# Super_Simple_Mosfet_H-Bridge.net
KiCad netlist of a schematic drawn in EAGLE
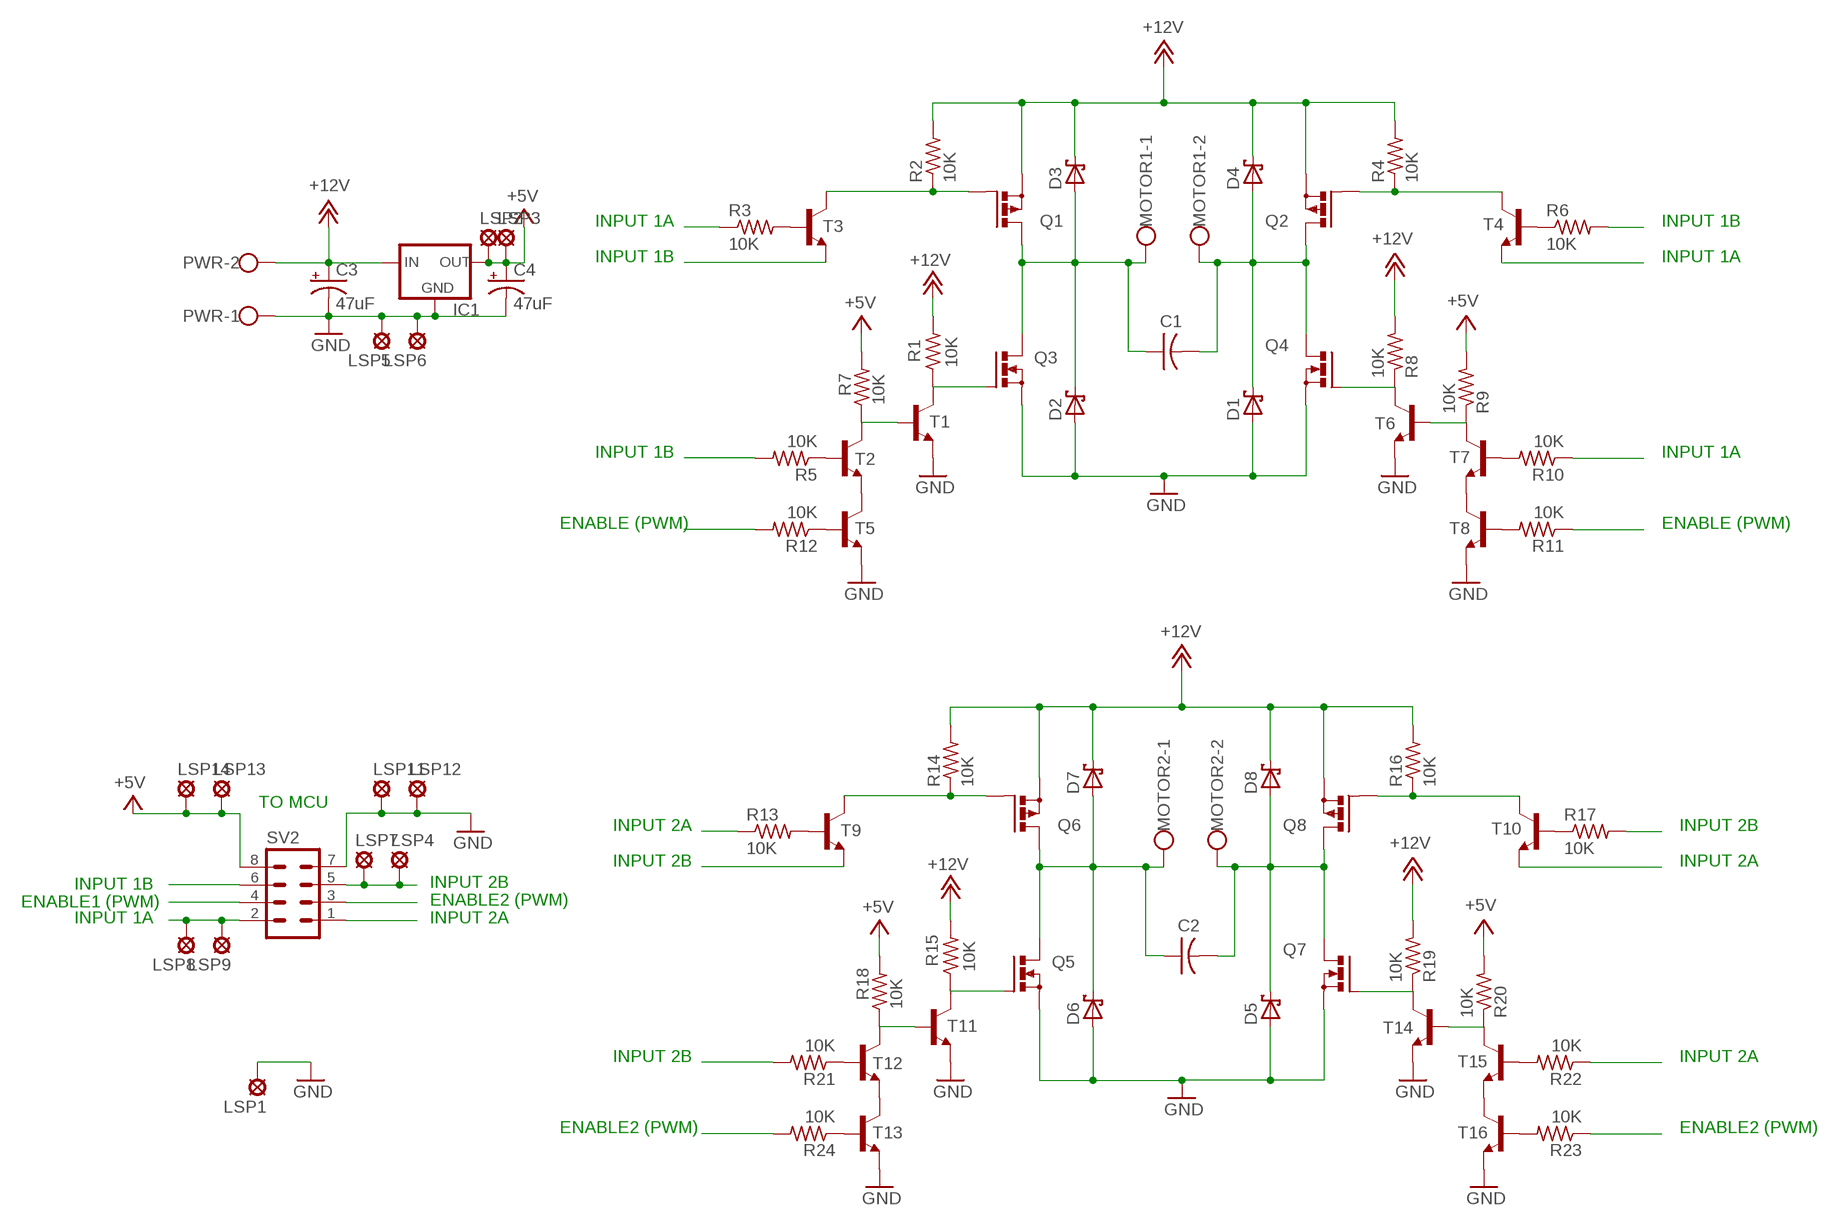
[diagram p0: schematic, sheet 1]

(export (version "E")
  (design (tool "Eeschema 10.0.6"))
  (components
    (comp (ref "C1")
      (value "C-US050-025X075")
      (footprint "eagle-import:C050-025X075")
      (libsource (lib "eagle-import") (part "C-US050-025X075"))
    )
    (comp (ref "C2")
      (value "C-US050-025X075")
      (footprint "eagle-import:C050-025X075")
      (libsource (lib "eagle-import") (part "C-US050-025X075"))
    )
    (comp (ref "C3")
      (value "47uF")
      (footprint "eagle-import:E2,5-6E")
      (libsource (lib "eagle-import") (part "CPOL-USE2,5-6E"))
    )
    (comp (ref "C4")
      (value "47uF")
      (footprint "eagle-import:E2,5-6E")
      (libsource (lib "eagle-import") (part "CPOL-USE2,5-6E"))
    )
    (comp (ref "D1")
      (value "1N5817-B")
      (footprint "eagle-import:DO41-7.6")
      (libsource (lib "eagle-import") (part "1N5817-B"))
    )
    (comp (ref "D2")
      (value "1N5817-B")
      (footprint "eagle-import:DO41-7.6")
      (libsource (lib "eagle-import") (part "1N5817-B"))
    )
    (comp (ref "D3")
      (value "1N5817-B")
      (footprint "eagle-import:DO41-7.6")
      (libsource (lib "eagle-import") (part "1N5817-B"))
    )
    (comp (ref "D4")
      (value "1N5817-B")
      (footprint "eagle-import:DO41-7.6")
      (libsource (lib "eagle-import") (part "1N5817-B"))
    )
    (comp (ref "D5")
      (value "1N5817-B")
      (footprint "eagle-import:DO41-7.6")
      (libsource (lib "eagle-import") (part "1N5817-B"))
    )
    (comp (ref "D6")
      (value "1N5817-B")
      (footprint "eagle-import:DO41-7.6")
      (libsource (lib "eagle-import") (part "1N5817-B"))
    )
    (comp (ref "D7")
      (value "1N5817-B")
      (footprint "eagle-import:DO41-7.6")
      (libsource (lib "eagle-import") (part "1N5817-B"))
    )
    (comp (ref "D8")
      (value "1N5817-B")
      (footprint "eagle-import:DO41-7.6")
      (libsource (lib "eagle-import") (part "1N5817-B"))
    )
    (comp (ref "IC1")
      (value "78XXS")
      (footprint "eagle-import:78XXS")
      (libsource (lib "eagle-import") (part "78XXS"))
    )
    (comp (ref "LSP1")
      (value "LSP13")
      (footprint "eagle-import:LSP13")
      (libsource (lib "eagle-import") (part "LSP13"))
    )
    (comp (ref "LSP2")
      (value "LSP13")
      (footprint "eagle-import:LSP13")
      (libsource (lib "eagle-import") (part "LSP13"))
    )
    (comp (ref "LSP3")
      (value "LSP13")
      (footprint "eagle-import:LSP13")
      (libsource (lib "eagle-import") (part "LSP13"))
    )
    (comp (ref "LSP4")
      (value "LSP13")
      (footprint "eagle-import:LSP13")
      (libsource (lib "eagle-import") (part "LSP13"))
    )
    (comp (ref "LSP5")
      (value "LSP13")
      (footprint "eagle-import:LSP13")
      (libsource (lib "eagle-import") (part "LSP13"))
    )
    (comp (ref "LSP6")
      (value "LSP13")
      (footprint "eagle-import:LSP13")
      (libsource (lib "eagle-import") (part "LSP13"))
    )
    (comp (ref "LSP7")
      (value "LSP13")
      (footprint "eagle-import:LSP13")
      (libsource (lib "eagle-import") (part "LSP13"))
    )
    (comp (ref "LSP8")
      (value "LSP13")
      (footprint "eagle-import:LSP13")
      (libsource (lib "eagle-import") (part "LSP13"))
    )
    (comp (ref "LSP9")
      (value "LSP13")
      (footprint "eagle-import:LSP13")
      (libsource (lib "eagle-import") (part "LSP13"))
    )
    (comp (ref "LSP11")
      (value "LSP13")
      (footprint "eagle-import:LSP13")
      (libsource (lib "eagle-import") (part "LSP13"))
    )
    (comp (ref "LSP12")
      (value "LSP13")
      (footprint "eagle-import:LSP13")
      (libsource (lib "eagle-import") (part "LSP13"))
    )
    (comp (ref "LSP13")
      (value "LSP13")
      (footprint "eagle-import:LSP13")
      (libsource (lib "eagle-import") (part "LSP13"))
    )
    (comp (ref "LSP14")
      (value "LSP13")
      (footprint "eagle-import:LSP13")
      (libsource (lib "eagle-import") (part "LSP13"))
    )
    (comp (ref "MOTOR1")
      (value "W237-102")
      (footprint "eagle-import:W237-102")
      (fields (field (name "MPN") "237-102"))
      (libsource (lib "eagle-import") (part "W237-102"))
    )
    (comp (ref "MOTOR2")
      (value "W237-102")
      (footprint "eagle-import:W237-102")
      (fields (field (name "MPN") "237-102"))
      (libsource (lib "eagle-import") (part "W237-102"))
    )
    (comp (ref "PWR")
      (value "W237-102")
      (footprint "eagle-import:W237-102")
      (fields (field (name "MPN") "237-102"))
      (libsource (lib "eagle-import") (part "W237-102"))
    )
    (comp (ref "Q1")
      (value "IRF9640")
      (footprint "eagle-import:TO220BV")
      (libsource (lib "eagle-import") (part "PMOSFET_PTO220BV"))
    )
    (comp (ref "Q2")
      (value "IRF9640")
      (footprint "eagle-import:TO220BV")
      (libsource (lib "eagle-import") (part "PMOSFET_PTO220BV"))
    )
    (comp (ref "Q3")
      (value "IRF530N")
      (footprint "eagle-import:TO220BV")
      (libsource (lib "eagle-import") (part "PMOSFET_NTO220BV"))
    )
    (comp (ref "Q4")
      (value "IRF530N")
      (footprint "eagle-import:TO220BV")
      (libsource (lib "eagle-import") (part "PMOSFET_NTO220BV"))
    )
    (comp (ref "Q5")
      (value "IRF530N")
      (footprint "eagle-import:TO220BV")
      (libsource (lib "eagle-import") (part "PMOSFET_NTO220BV"))
    )
    (comp (ref "Q6")
      (value "IRF9640")
      (footprint "eagle-import:TO220BV")
      (libsource (lib "eagle-import") (part "PMOSFET_PTO220BV"))
    )
    (comp (ref "Q7")
      (value "IRF530N")
      (footprint "eagle-import:TO220BV")
      (libsource (lib "eagle-import") (part "PMOSFET_NTO220BV"))
    )
    (comp (ref "Q8")
      (value "IRF9640")
      (footprint "eagle-import:TO220BV")
      (libsource (lib "eagle-import") (part "PMOSFET_PTO220BV"))
    )
    (comp (ref "R1")
      (value "10K")
      (footprint "eagle-import:0207_10")
      (libsource (lib "eagle-import") (part "R-US_0207/10"))
    )
    (comp (ref "R2")
      (value "10K")
      (footprint "eagle-import:0207_10")
      (libsource (lib "eagle-import") (part "R-US_0207/10"))
    )
    (comp (ref "R3")
      (value "10K")
      (footprint "eagle-import:0207_10")
      (libsource (lib "eagle-import") (part "R-US_0207/10"))
    )
    (comp (ref "R4")
      (value "10K")
      (footprint "eagle-import:0207_10")
      (libsource (lib "eagle-import") (part "R-US_0207/10"))
    )
    (comp (ref "R5")
      (value "10K")
      (footprint "eagle-import:0207_10")
      (libsource (lib "eagle-import") (part "R-US_0207/10"))
    )
    (comp (ref "R6")
      (value "10K")
      (footprint "eagle-import:0207_10")
      (libsource (lib "eagle-import") (part "R-US_0207/10"))
    )
    (comp (ref "R7")
      (value "10K")
      (footprint "eagle-import:0207_10")
      (libsource (lib "eagle-import") (part "R-US_0207/10"))
    )
    (comp (ref "R8")
      (value "10K")
      (footprint "eagle-import:0207_10")
      (libsource (lib "eagle-import") (part "R-US_0207/10"))
    )
    (comp (ref "R9")
      (value "10K")
      (footprint "eagle-import:0207_10")
      (libsource (lib "eagle-import") (part "R-US_0207/10"))
    )
    (comp (ref "R10")
      (value "10K")
      (footprint "eagle-import:0207_10")
      (libsource (lib "eagle-import") (part "R-US_0207/10"))
    )
    (comp (ref "R11")
      (value "10K")
      (footprint "eagle-import:0207_10")
      (libsource (lib "eagle-import") (part "R-US_0207/10"))
    )
    (comp (ref "R12")
      (value "10K")
      (footprint "eagle-import:0207_10")
      (libsource (lib "eagle-import") (part "R-US_0207/10"))
    )
    (comp (ref "R13")
      (value "10K")
      (footprint "eagle-import:0207_10")
      (libsource (lib "eagle-import") (part "R-US_0207/10"))
    )
    (comp (ref "R14")
      (value "10K")
      (footprint "eagle-import:0207_10")
      (libsource (lib "eagle-import") (part "R-US_0207/10"))
    )
    (comp (ref "R15")
      (value "10K")
      (footprint "eagle-import:0207_10")
      (libsource (lib "eagle-import") (part "R-US_0207/10"))
    )
    (comp (ref "R16")
      (value "10K")
      (footprint "eagle-import:0207_10")
      (libsource (lib "eagle-import") (part "R-US_0207/10"))
    )
    (comp (ref "R17")
      (value "10K")
      (footprint "eagle-import:0207_10")
      (libsource (lib "eagle-import") (part "R-US_0207/10"))
    )
    (comp (ref "R18")
      (value "10K")
      (footprint "eagle-import:0207_10")
      (libsource (lib "eagle-import") (part "R-US_0207/10"))
    )
    (comp (ref "R19")
      (value "10K")
      (footprint "eagle-import:0207_10")
      (libsource (lib "eagle-import") (part "R-US_0207/10"))
    )
    (comp (ref "R20")
      (value "10K")
      (footprint "eagle-import:0207_10")
      (libsource (lib "eagle-import") (part "R-US_0207/10"))
    )
    (comp (ref "R21")
      (value "10K")
      (footprint "eagle-import:0207_10")
      (libsource (lib "eagle-import") (part "R-US_0207/10"))
    )
    (comp (ref "R22")
      (value "10K")
      (footprint "eagle-import:0207_10")
      (libsource (lib "eagle-import") (part "R-US_0207/10"))
    )
    (comp (ref "R23")
      (value "10K")
      (footprint "eagle-import:0207_10")
      (libsource (lib "eagle-import") (part "R-US_0207/10"))
    )
    (comp (ref "R24")
      (value "10K")
      (footprint "eagle-import:0207_10")
      (libsource (lib "eagle-import") (part "R-US_0207/10"))
    )
    (comp (ref "SV2")
      (value "MA04-2")
      (footprint "eagle-import:MA04-2")
      (libsource (lib "eagle-import") (part "MA04-2"))
    )
    (comp (ref "T1")
      (value "-NPN-TO92-EBC")
      (footprint "eagle-import:TO92-EBC")
      (libsource (lib "eagle-import") (part "-NPN-TO92-EBC"))
    )
    (comp (ref "T2")
      (value "-NPN-TO92-EBC")
      (footprint "eagle-import:TO92-EBC")
      (libsource (lib "eagle-import") (part "-NPN-TO92-EBC"))
    )
    (comp (ref "T3")
      (value "-NPN-TO92-EBC")
      (footprint "eagle-import:TO92-EBC")
      (libsource (lib "eagle-import") (part "-NPN-TO92-EBC"))
    )
    (comp (ref "T4")
      (value "-NPN-TO92-EBC")
      (footprint "eagle-import:TO92-EBC")
      (libsource (lib "eagle-import") (part "-NPN-TO92-EBC"))
    )
    (comp (ref "T5")
      (value "-NPN-TO92-EBC")
      (footprint "eagle-import:TO92-EBC")
      (libsource (lib "eagle-import") (part "-NPN-TO92-EBC"))
    )
    (comp (ref "T6")
      (value "-NPN-TO92-EBC")
      (footprint "eagle-import:TO92-EBC")
      (libsource (lib "eagle-import") (part "-NPN-TO92-EBC"))
    )
    (comp (ref "T7")
      (value "-NPN-TO92-EBC")
      (footprint "eagle-import:TO92-EBC")
      (libsource (lib "eagle-import") (part "-NPN-TO92-EBC"))
    )
    (comp (ref "T8")
      (value "-NPN-TO92-EBC")
      (footprint "eagle-import:TO92-EBC")
      (libsource (lib "eagle-import") (part "-NPN-TO92-EBC"))
    )
    (comp (ref "T9")
      (value "-NPN-TO92-EBC")
      (footprint "eagle-import:TO92-EBC")
      (libsource (lib "eagle-import") (part "-NPN-TO92-EBC"))
    )
    (comp (ref "T10")
      (value "-NPN-TO92-EBC")
      (footprint "eagle-import:TO92-EBC")
      (libsource (lib "eagle-import") (part "-NPN-TO92-EBC"))
    )
    (comp (ref "T11")
      (value "-NPN-TO92-EBC")
      (footprint "eagle-import:TO92-EBC")
      (libsource (lib "eagle-import") (part "-NPN-TO92-EBC"))
    )
    (comp (ref "T12")
      (value "-NPN-TO92-EBC")
      (footprint "eagle-import:TO92-EBC")
      (libsource (lib "eagle-import") (part "-NPN-TO92-EBC"))
    )
    (comp (ref "T13")
      (value "-NPN-TO92-EBC")
      (footprint "eagle-import:TO92-EBC")
      (libsource (lib "eagle-import") (part "-NPN-TO92-EBC"))
    )
    (comp (ref "T14")
      (value "-NPN-TO92-EBC")
      (footprint "eagle-import:TO92-EBC")
      (libsource (lib "eagle-import") (part "-NPN-TO92-EBC"))
    )
    (comp (ref "T15")
      (value "-NPN-TO92-EBC")
      (footprint "eagle-import:TO92-EBC")
      (libsource (lib "eagle-import") (part "-NPN-TO92-EBC"))
    )
    (comp (ref "T16")
      (value "-NPN-TO92-EBC")
      (footprint "eagle-import:TO92-EBC")
      (libsource (lib "eagle-import") (part "-NPN-TO92-EBC"))
    )
  )
  (nets
    (net (code "1") (name "+5V") (class "Default")
      (node (ref "C4") (pin "+") (pinfunction "+_+") (pintype "passive"))
      (node (ref "IC1") (pin "OUT") (pinfunction "OUT_OUT") (pintype "passive"))
      (node (ref "LSP13") (pin "MP") (pinfunction "MP_MP") (pintype "passive"))
      (node (ref "LSP14") (pin "MP") (pinfunction "MP_MP") (pintype "passive"))
      (node (ref "LSP2") (pin "MP") (pinfunction "MP_MP") (pintype "passive"))
      (node (ref "LSP3") (pin "MP") (pinfunction "MP_MP") (pintype "passive"))
      (node (ref "R18") (pin "2") (pinfunction "2_2") (pintype "passive"))
      (node (ref "R20") (pin "2") (pinfunction "2_2") (pintype "passive"))
      (node (ref "R7") (pin "2") (pinfunction "2_2") (pintype "passive"))
      (node (ref "R9") (pin "2") (pinfunction "2_2") (pintype "passive"))
      (node (ref "SV2") (pin "8") (pinfunction "8_8") (pintype "passive"))
    )
    (net (code "2") (name "+12V") (class "Default")
      (node (ref "C3") (pin "+") (pinfunction "+_+") (pintype "passive"))
      (node (ref "D3") (pin "C") (pinfunction "C_C") (pintype "passive"))
      (node (ref "D4") (pin "C") (pinfunction "C_C") (pintype "passive"))
      (node (ref "D7") (pin "C") (pinfunction "C_C") (pintype "passive"))
      (node (ref "D8") (pin "C") (pinfunction "C_C") (pintype "passive"))
      (node (ref "IC1") (pin "IN") (pinfunction "IN_IN") (pintype "input"))
      (node (ref "PWR") (pin "2") (pinfunction "KL_2") (pintype "passive"))
      (node (ref "Q1") (pin "S") (pinfunction "S_S") (pintype "passive"))
      (node (ref "Q2") (pin "S") (pinfunction "S_S") (pintype "passive"))
      (node (ref "Q6") (pin "S") (pinfunction "S_S") (pintype "passive"))
      (node (ref "Q8") (pin "S") (pinfunction "S_S") (pintype "passive"))
      (node (ref "R1") (pin "2") (pinfunction "2_2") (pintype "passive"))
      (node (ref "R14") (pin "2") (pinfunction "2_2") (pintype "passive"))
      (node (ref "R15") (pin "2") (pinfunction "2_2") (pintype "passive"))
      (node (ref "R16") (pin "2") (pinfunction "2_2") (pintype "passive"))
      (node (ref "R19") (pin "2") (pinfunction "2_2") (pintype "passive"))
      (node (ref "R2") (pin "2") (pinfunction "2_2") (pintype "passive"))
      (node (ref "R4") (pin "2") (pinfunction "2_2") (pintype "passive"))
      (node (ref "R8") (pin "2") (pinfunction "2_2") (pintype "passive"))
    )
    (net (code "3") (name "/1A") (class "Default")
      (node (ref "LSP8") (pin "MP") (pinfunction "MP_MP") (pintype "passive"))
      (node (ref "LSP9") (pin "MP") (pinfunction "MP_MP") (pintype "passive"))
      (node (ref "R10") (pin "1") (pinfunction "1_1") (pintype "passive"))
      (node (ref "R3") (pin "1") (pinfunction "1_1") (pintype "passive"))
      (node (ref "SV2") (pin "2") (pinfunction "2_2") (pintype "passive"))
      (node (ref "T4") (pin "E") (pinfunction "E_E") (pintype "passive"))
    )
    (net (code "4") (name "/1B") (class "Default")
      (node (ref "R5") (pin "2") (pinfunction "2_2") (pintype "passive"))
      (node (ref "R6") (pin "2") (pinfunction "2_2") (pintype "passive"))
      (node (ref "SV2") (pin "6") (pinfunction "6_6") (pintype "passive"))
      (node (ref "T3") (pin "E") (pinfunction "E_E") (pintype "passive"))
    )
    (net (code "5") (name "/2A") (class "Default")
      (node (ref "R13") (pin "1") (pinfunction "1_1") (pintype "passive"))
      (node (ref "R22") (pin "1") (pinfunction "1_1") (pintype "passive"))
      (node (ref "SV2") (pin "1") (pinfunction "1_1") (pintype "passive"))
      (node (ref "T10") (pin "E") (pinfunction "E_E") (pintype "passive"))
    )
    (net (code "6") (name "/2B") (class "Default")
      (node (ref "LSP4") (pin "MP") (pinfunction "MP_MP") (pintype "passive"))
      (node (ref "LSP7") (pin "MP") (pinfunction "MP_MP") (pintype "passive"))
      (node (ref "R17") (pin "2") (pinfunction "2_2") (pintype "passive"))
      (node (ref "R21") (pin "2") (pinfunction "2_2") (pintype "passive"))
      (node (ref "SV2") (pin "5") (pinfunction "5_5") (pintype "passive"))
      (node (ref "T9") (pin "E") (pinfunction "E_E") (pintype "passive"))
    )
    (net (code "7") (name "/ENABLE1") (class "Default")
      (node (ref "R11") (pin "1") (pinfunction "1_1") (pintype "passive"))
      (node (ref "R12") (pin "2") (pinfunction "2_2") (pintype "passive"))
      (node (ref "SV2") (pin "4") (pinfunction "4_4") (pintype "passive"))
    )
    (net (code "8") (name "/ENABLE2") (class "Default")
      (node (ref "R23") (pin "1") (pinfunction "1_1") (pintype "passive"))
      (node (ref "R24") (pin "2") (pinfunction "2_2") (pintype "passive"))
      (node (ref "SV2") (pin "3") (pinfunction "3_3") (pintype "passive"))
    )
    (net (code "9") (name "GND") (class "Default")
      (node (ref "C3") (pin "-") (pinfunction "-_-") (pintype "passive"))
      (node (ref "C4") (pin "-") (pinfunction "-_-") (pintype "passive"))
      (node (ref "D1") (pin "A") (pinfunction "A_A") (pintype "passive"))
      (node (ref "D2") (pin "A") (pinfunction "A_A") (pintype "passive"))
      (node (ref "D5") (pin "A") (pinfunction "A_A") (pintype "passive"))
      (node (ref "D6") (pin "A") (pinfunction "A_A") (pintype "passive"))
      (node (ref "IC1") (pin "GND") (pinfunction "GND_GND") (pintype "input"))
      (node (ref "LSP1") (pin "MP") (pinfunction "MP_MP") (pintype "passive"))
      (node (ref "LSP11") (pin "MP") (pinfunction "MP_MP") (pintype "passive"))
      (node (ref "LSP12") (pin "MP") (pinfunction "MP_MP") (pintype "passive"))
      (node (ref "LSP5") (pin "MP") (pinfunction "MP_MP") (pintype "passive"))
      (node (ref "LSP6") (pin "MP") (pinfunction "MP_MP") (pintype "passive"))
      (node (ref "PWR") (pin "1") (pinfunction "KL_1") (pintype "passive"))
      (node (ref "Q3") (pin "S") (pinfunction "S_S") (pintype "passive"))
      (node (ref "Q4") (pin "S") (pinfunction "S_S") (pintype "passive"))
      (node (ref "Q5") (pin "S") (pinfunction "S_S") (pintype "passive"))
      (node (ref "Q7") (pin "S") (pinfunction "S_S") (pintype "passive"))
      (node (ref "SV2") (pin "7") (pinfunction "7_7") (pintype "passive"))
      (node (ref "T1") (pin "E") (pinfunction "E_E") (pintype "passive"))
      (node (ref "T11") (pin "E") (pinfunction "E_E") (pintype "passive"))
      (node (ref "T13") (pin "E") (pinfunction "E_E") (pintype "passive"))
      (node (ref "T14") (pin "E") (pinfunction "E_E") (pintype "passive"))
      (node (ref "T16") (pin "E") (pinfunction "E_E") (pintype "passive"))
      (node (ref "T5") (pin "E") (pinfunction "E_E") (pintype "passive"))
      (node (ref "T6") (pin "E") (pinfunction "E_E") (pintype "passive"))
      (node (ref "T8") (pin "E") (pinfunction "E_E") (pintype "passive"))
    )
    (net (code "10") (name "Net-(MOTOR1A-KL)") (class "Default")
      (node (ref "C1") (pin "1") (pinfunction "1_1") (pintype "passive"))
      (node (ref "D2") (pin "C") (pinfunction "C_C") (pintype "passive"))
      (node (ref "D3") (pin "A") (pinfunction "A_A") (pintype "passive"))
      (node (ref "MOTOR1") (pin "1") (pinfunction "KL_1") (pintype "passive"))
      (node (ref "Q1") (pin "D") (pinfunction "D_D") (pintype "passive"))
      (node (ref "Q3") (pin "D") (pinfunction "D_D") (pintype "passive"))
    )
    (net (code "11") (name "Net-(MOTOR1B-KL)") (class "Default")
      (node (ref "C1") (pin "2") (pinfunction "2_2") (pintype "passive"))
      (node (ref "D1") (pin "C") (pinfunction "C_C") (pintype "passive"))
      (node (ref "D4") (pin "A") (pinfunction "A_A") (pintype "passive"))
      (node (ref "MOTOR1") (pin "2") (pinfunction "KL_2") (pintype "passive"))
      (node (ref "Q2") (pin "D") (pinfunction "D_D") (pintype "passive"))
      (node (ref "Q4") (pin "D") (pinfunction "D_D") (pintype "passive"))
    )
    (net (code "12") (name "Net-(MOTOR2A-KL)") (class "Default")
      (node (ref "C2") (pin "1") (pinfunction "1_1") (pintype "passive"))
      (node (ref "D6") (pin "C") (pinfunction "C_C") (pintype "passive"))
      (node (ref "D7") (pin "A") (pinfunction "A_A") (pintype "passive"))
      (node (ref "MOTOR2") (pin "1") (pinfunction "KL_1") (pintype "passive"))
      (node (ref "Q5") (pin "D") (pinfunction "D_D") (pintype "passive"))
      (node (ref "Q6") (pin "D") (pinfunction "D_D") (pintype "passive"))
    )
    (net (code "13") (name "Net-(MOTOR2B-KL)") (class "Default")
      (node (ref "C2") (pin "2") (pinfunction "2_2") (pintype "passive"))
      (node (ref "D5") (pin "C") (pinfunction "C_C") (pintype "passive"))
      (node (ref "D8") (pin "A") (pinfunction "A_A") (pintype "passive"))
      (node (ref "MOTOR2") (pin "2") (pinfunction "KL_2") (pintype "passive"))
      (node (ref "Q7") (pin "D") (pinfunction "D_D") (pintype "passive"))
      (node (ref "Q8") (pin "D") (pinfunction "D_D") (pintype "passive"))
    )
    (net (code "14") (name "Net-(Q1-PadG)") (class "Default")
      (node (ref "Q1") (pin "G") (pinfunction "G_G") (pintype "passive"))
      (node (ref "R2") (pin "1") (pinfunction "1_1") (pintype "passive"))
      (node (ref "T3") (pin "C") (pinfunction "C_C") (pintype "passive"))
    )
    (net (code "15") (name "Net-(Q2-PadG)") (class "Default")
      (node (ref "Q2") (pin "G") (pinfunction "G_G") (pintype "passive"))
      (node (ref "R4") (pin "1") (pinfunction "1_1") (pintype "passive"))
      (node (ref "T4") (pin "C") (pinfunction "C_C") (pintype "passive"))
    )
    (net (code "16") (name "Net-(Q3-PadG)") (class "Default")
      (node (ref "Q3") (pin "G") (pinfunction "G_G") (pintype "passive"))
      (node (ref "R1") (pin "1") (pinfunction "1_1") (pintype "passive"))
      (node (ref "T1") (pin "C") (pinfunction "C_C") (pintype "passive"))
    )
    (net (code "17") (name "Net-(Q4-PadG)") (class "Default")
      (node (ref "Q4") (pin "G") (pinfunction "G_G") (pintype "passive"))
      (node (ref "R8") (pin "1") (pinfunction "1_1") (pintype "passive"))
      (node (ref "T6") (pin "C") (pinfunction "C_C") (pintype "passive"))
    )
    (net (code "18") (name "Net-(Q5-PadG)") (class "Default")
      (node (ref "Q5") (pin "G") (pinfunction "G_G") (pintype "passive"))
      (node (ref "R15") (pin "1") (pinfunction "1_1") (pintype "passive"))
      (node (ref "T11") (pin "C") (pinfunction "C_C") (pintype "passive"))
    )
    (net (code "19") (name "Net-(Q6-PadG)") (class "Default")
      (node (ref "Q6") (pin "G") (pinfunction "G_G") (pintype "passive"))
      (node (ref "R14") (pin "1") (pinfunction "1_1") (pintype "passive"))
      (node (ref "T9") (pin "C") (pinfunction "C_C") (pintype "passive"))
    )
    (net (code "20") (name "Net-(Q7-PadG)") (class "Default")
      (node (ref "Q7") (pin "G") (pinfunction "G_G") (pintype "passive"))
      (node (ref "R19") (pin "1") (pinfunction "1_1") (pintype "passive"))
      (node (ref "T14") (pin "C") (pinfunction "C_C") (pintype "passive"))
    )
    (net (code "21") (name "Net-(Q8-PadG)") (class "Default")
      (node (ref "Q8") (pin "G") (pinfunction "G_G") (pintype "passive"))
      (node (ref "R16") (pin "1") (pinfunction "1_1") (pintype "passive"))
      (node (ref "T10") (pin "C") (pinfunction "C_C") (pintype "passive"))
    )
    (net (code "22") (name "Net-(R3-Pad2)") (class "Default")
      (node (ref "R3") (pin "2") (pinfunction "2_2") (pintype "passive"))
      (node (ref "T3") (pin "B") (pinfunction "B_B") (pintype "passive"))
    )
    (net (code "23") (name "Net-(R5-Pad1)") (class "Default")
      (node (ref "R5") (pin "1") (pinfunction "1_1") (pintype "passive"))
      (node (ref "T2") (pin "B") (pinfunction "B_B") (pintype "passive"))
    )
    (net (code "24") (name "Net-(R6-Pad1)") (class "Default")
      (node (ref "R6") (pin "1") (pinfunction "1_1") (pintype "passive"))
      (node (ref "T4") (pin "B") (pinfunction "B_B") (pintype "passive"))
    )
    (net (code "25") (name "Net-(R7-Pad1)") (class "Default")
      (node (ref "R7") (pin "1") (pinfunction "1_1") (pintype "passive"))
      (node (ref "T1") (pin "B") (pinfunction "B_B") (pintype "passive"))
      (node (ref "T2") (pin "C") (pinfunction "C_C") (pintype "passive"))
    )
    (net (code "26") (name "Net-(R9-Pad1)") (class "Default")
      (node (ref "R9") (pin "1") (pinfunction "1_1") (pintype "passive"))
      (node (ref "T6") (pin "B") (pinfunction "B_B") (pintype "passive"))
      (node (ref "T7") (pin "C") (pinfunction "C_C") (pintype "passive"))
    )
    (net (code "27") (name "Net-(R10-Pad2)") (class "Default")
      (node (ref "R10") (pin "2") (pinfunction "2_2") (pintype "passive"))
      (node (ref "T7") (pin "B") (pinfunction "B_B") (pintype "passive"))
    )
    (net (code "28") (name "Net-(R11-Pad2)") (class "Default")
      (node (ref "R11") (pin "2") (pinfunction "2_2") (pintype "passive"))
      (node (ref "T8") (pin "B") (pinfunction "B_B") (pintype "passive"))
    )
    (net (code "29") (name "Net-(R12-Pad1)") (class "Default")
      (node (ref "R12") (pin "1") (pinfunction "1_1") (pintype "passive"))
      (node (ref "T5") (pin "B") (pinfunction "B_B") (pintype "passive"))
    )
    (net (code "30") (name "Net-(R13-Pad2)") (class "Default")
      (node (ref "R13") (pin "2") (pinfunction "2_2") (pintype "passive"))
      (node (ref "T9") (pin "B") (pinfunction "B_B") (pintype "passive"))
    )
    (net (code "31") (name "Net-(R17-Pad1)") (class "Default")
      (node (ref "R17") (pin "1") (pinfunction "1_1") (pintype "passive"))
      (node (ref "T10") (pin "B") (pinfunction "B_B") (pintype "passive"))
    )
    (net (code "32") (name "Net-(R18-Pad1)") (class "Default")
      (node (ref "R18") (pin "1") (pinfunction "1_1") (pintype "passive"))
      (node (ref "T11") (pin "B") (pinfunction "B_B") (pintype "passive"))
      (node (ref "T12") (pin "C") (pinfunction "C_C") (pintype "passive"))
    )
    (net (code "33") (name "Net-(R20-Pad1)") (class "Default")
      (node (ref "R20") (pin "1") (pinfunction "1_1") (pintype "passive"))
      (node (ref "T14") (pin "B") (pinfunction "B_B") (pintype "passive"))
      (node (ref "T15") (pin "C") (pinfunction "C_C") (pintype "passive"))
    )
    (net (code "34") (name "Net-(R21-Pad1)") (class "Default")
      (node (ref "R21") (pin "1") (pinfunction "1_1") (pintype "passive"))
      (node (ref "T12") (pin "B") (pinfunction "B_B") (pintype "passive"))
    )
    (net (code "35") (name "Net-(R22-Pad2)") (class "Default")
      (node (ref "R22") (pin "2") (pinfunction "2_2") (pintype "passive"))
      (node (ref "T15") (pin "B") (pinfunction "B_B") (pintype "passive"))
    )
    (net (code "36") (name "Net-(R23-Pad2)") (class "Default")
      (node (ref "R23") (pin "2") (pinfunction "2_2") (pintype "passive"))
      (node (ref "T16") (pin "B") (pinfunction "B_B") (pintype "passive"))
    )
    (net (code "37") (name "Net-(R24-Pad1)") (class "Default")
      (node (ref "R24") (pin "1") (pinfunction "1_1") (pintype "passive"))
      (node (ref "T13") (pin "B") (pinfunction "B_B") (pintype "passive"))
    )
    (net (code "38") (name "Net-(T2-PadE)") (class "Default")
      (node (ref "T2") (pin "E") (pinfunction "E_E") (pintype "passive"))
      (node (ref "T5") (pin "C") (pinfunction "C_C") (pintype "passive"))
    )
    (net (code "39") (name "Net-(T7-PadE)") (class "Default")
      (node (ref "T7") (pin "E") (pinfunction "E_E") (pintype "passive"))
      (node (ref "T8") (pin "C") (pinfunction "C_C") (pintype "passive"))
    )
    (net (code "40") (name "Net-(T12-PadE)") (class "Default")
      (node (ref "T12") (pin "E") (pinfunction "E_E") (pintype "passive"))
      (node (ref "T13") (pin "C") (pinfunction "C_C") (pintype "passive"))
    )
    (net (code "41") (name "Net-(T15-PadE)") (class "Default")
      (node (ref "T15") (pin "E") (pinfunction "E_E") (pintype "passive"))
      (node (ref "T16") (pin "C") (pinfunction "C_C") (pintype "passive"))
    )
  )
)
